# SCH_V1.net
KiCad netlist of a schematic drawn in Altium Designer
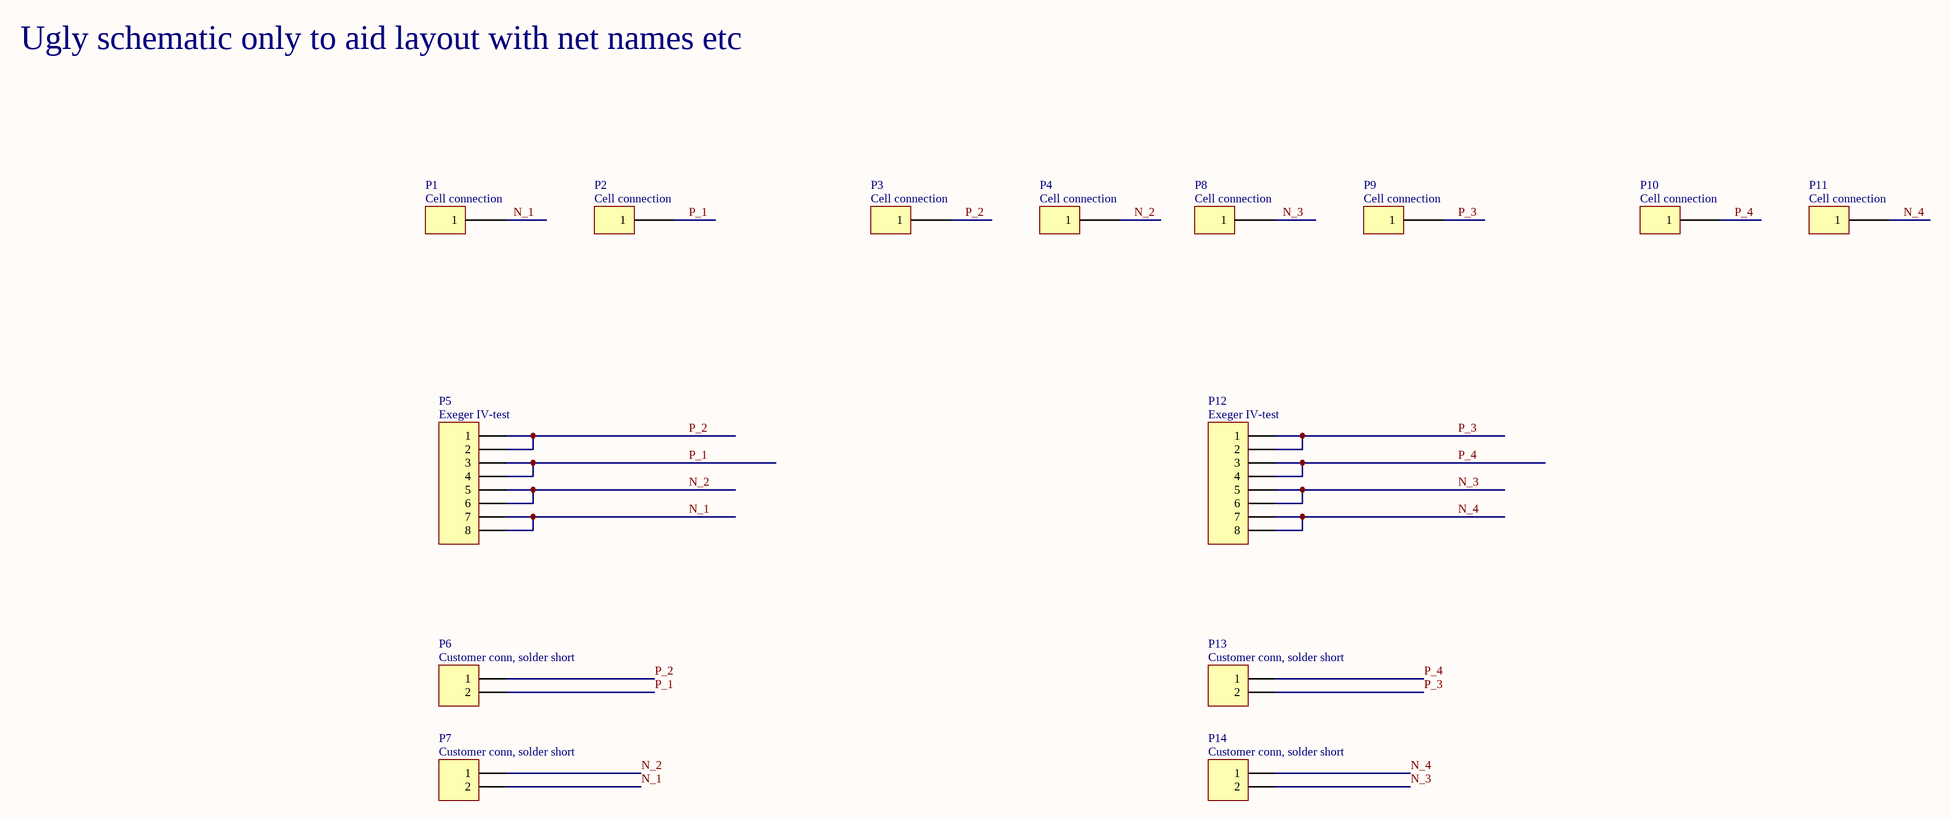
[diagram p0: SCH_V1.SchDoc]

(export (version "E")
  (design (tool "Eeschema 10.0.6"))
  (components
    (comp (ref "P1")
      (value "Cell connection")
      (footprint "Cell_pad_4mm_SM0.5mm")
      (libsource (lib "Flex_SCH_symbols") (part "Cell connection 1P"))
    )
    (comp (ref "P2")
      (value "Cell connection")
      (footprint "Cell_pad_4mm_SM0.5mm")
      (libsource (lib "Flex_SCH_symbols") (part "Cell connection 1P"))
    )
    (comp (ref "P3")
      (value "Cell connection")
      (footprint "Cell_pad_4mm_SM0.5mm")
      (libsource (lib "Flex_SCH_symbols") (part "Cell connection 1P"))
    )
    (comp (ref "P4")
      (value "Cell connection")
      (footprint "Cell_pad_4mm_SM0.5mm")
      (libsource (lib "Flex_SCH_symbols") (part "Cell connection 1P"))
    )
    (comp (ref "P5")
      (value "Exeger IV-test")
      (footprint "EXEGER_IV_8_PIN_NO_STIFF_ISOL_0.4")
      (description "Header, 8-Pin")
      (libsource (lib "Miscellaneous Connectors") (part "Header 8"))
    )
    (comp (ref "P6")
      (value "Customer conn, solder short")
      (footprint "Customer_2022_solder_short_ISOL_0.4_S")
      (description "Header, 2-Pin")
      (libsource (lib "Miscellaneous Connectors") (part "Header 2"))
    )
    (comp (ref "P7")
      (value "Customer conn, solder short")
      (footprint "Customer_2022_solder_short_ISOL_0.4_S")
      (description "Header, 2-Pin")
      (libsource (lib "Miscellaneous Connectors") (part "Header 2"))
    )
    (comp (ref "P8")
      (value "Cell connection")
      (footprint "Cell_pad_4mm_SM0.5mm")
      (libsource (lib "Flex_SCH_symbols") (part "Cell connection 1P"))
    )
    (comp (ref "P9")
      (value "Cell connection")
      (footprint "Cell_pad_4mm_SM0.5mm")
      (libsource (lib "Flex_SCH_symbols") (part "Cell connection 1P"))
    )
    (comp (ref "P10")
      (value "Cell connection")
      (footprint "Cell_pad_4mm_SM0.5mm")
      (libsource (lib "Flex_SCH_symbols") (part "Cell connection 1P"))
    )
    (comp (ref "P11")
      (value "Cell connection")
      (footprint "Cell_pad_4mm_SM0.5mm")
      (libsource (lib "Flex_SCH_symbols") (part "Cell connection 1P"))
    )
    (comp (ref "P12")
      (value "Exeger IV-test")
      (footprint "EXEGER_IV_8_PIN_NO_STIFF_ISOL_0.4")
      (description "Header, 8-Pin")
      (libsource (lib "Miscellaneous Connectors") (part "Header 8"))
    )
    (comp (ref "P13")
      (value "Customer conn, solder short")
      (footprint "Customer_2022_solder_short_ISOL_0.4_S")
      (description "Header, 2-Pin")
      (libsource (lib "Miscellaneous Connectors") (part "Header 2"))
    )
    (comp (ref "P14")
      (value "Customer conn, solder short")
      (footprint "Customer_2022_solder_short_ISOL_0.4_S")
      (description "Header, 2-Pin")
      (libsource (lib "Miscellaneous Connectors") (part "Header 2"))
    )
  )
  (nets
    (net (code "1") (name "/N_1") (class "Default")
      (node (ref "P1") (pin "1") (pinfunction "1_1") (pintype "passive"))
      (node (ref "P5") (pin "7") (pinfunction "7_7") (pintype "passive"))
      (node (ref "P5") (pin "8") (pinfunction "8_8") (pintype "passive"))
      (node (ref "P7") (pin "2") (pinfunction "2_2") (pintype "passive"))
    )
    (net (code "2") (name "/N_2") (class "Default")
      (node (ref "P4") (pin "1") (pinfunction "1_1") (pintype "passive"))
      (node (ref "P5") (pin "5") (pinfunction "5_5") (pintype "passive"))
      (node (ref "P5") (pin "6") (pinfunction "6_6") (pintype "passive"))
      (node (ref "P7") (pin "1") (pinfunction "1_1") (pintype "passive"))
    )
    (net (code "3") (name "/N_3") (class "Default")
      (node (ref "P12") (pin "5") (pinfunction "5_5") (pintype "passive"))
      (node (ref "P12") (pin "6") (pinfunction "6_6") (pintype "passive"))
      (node (ref "P14") (pin "2") (pinfunction "2_2") (pintype "passive"))
      (node (ref "P8") (pin "1") (pinfunction "1_1") (pintype "passive"))
    )
    (net (code "4") (name "/N_4") (class "Default")
      (node (ref "P11") (pin "1") (pinfunction "1_1") (pintype "passive"))
      (node (ref "P12") (pin "7") (pinfunction "7_7") (pintype "passive"))
      (node (ref "P12") (pin "8") (pinfunction "8_8") (pintype "passive"))
      (node (ref "P14") (pin "1") (pinfunction "1_1") (pintype "passive"))
    )
    (net (code "5") (name "/P_1") (class "Default")
      (node (ref "P2") (pin "1") (pinfunction "1_1") (pintype "passive"))
      (node (ref "P5") (pin "3") (pinfunction "3_3") (pintype "passive"))
      (node (ref "P5") (pin "4") (pinfunction "4_4") (pintype "passive"))
      (node (ref "P6") (pin "2") (pinfunction "2_2") (pintype "passive"))
    )
    (net (code "6") (name "/P_2") (class "Default")
      (node (ref "P3") (pin "1") (pinfunction "1_1") (pintype "passive"))
      (node (ref "P5") (pin "1") (pinfunction "1_1") (pintype "passive"))
      (node (ref "P5") (pin "2") (pinfunction "2_2") (pintype "passive"))
      (node (ref "P6") (pin "1") (pinfunction "1_1") (pintype "passive"))
    )
    (net (code "7") (name "/P_3") (class "Default")
      (node (ref "P12") (pin "1") (pinfunction "1_1") (pintype "passive"))
      (node (ref "P12") (pin "2") (pinfunction "2_2") (pintype "passive"))
      (node (ref "P13") (pin "2") (pinfunction "2_2") (pintype "passive"))
      (node (ref "P9") (pin "1") (pinfunction "1_1") (pintype "passive"))
    )
    (net (code "8") (name "/P_4") (class "Default")
      (node (ref "P10") (pin "1") (pinfunction "1_1") (pintype "passive"))
      (node (ref "P12") (pin "3") (pinfunction "3_3") (pintype "passive"))
      (node (ref "P12") (pin "4") (pinfunction "4_4") (pintype "passive"))
      (node (ref "P13") (pin "1") (pinfunction "1_1") (pintype "passive"))
    )
  )
)
